# RMS_to_DC.net
KiCad netlist of a schematic drawn in Altium Designer
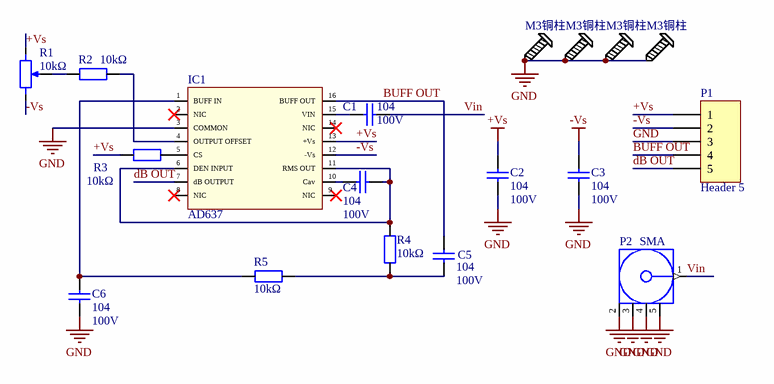
[diagram p0: RMS_to_DC.SchDoc]

(export (version "E")
  (design (tool "Eeschema 10.0.6"))
  (components
    (comp (ref "C1")
      (value "叠层陶瓷电容")
      (footprint "C0603")
      (description "无极性电容")
      (fields (field (name "CAPACITY") "104") (field (name "VOLTAGE") "100V"))
      (libsource (lib "原理图库") (part "104"))
    )
    (comp (ref "C2")
      (value "叠层陶瓷电容")
      (footprint "C0603")
      (description "无极性电容")
      (fields (field (name "CAPACITY") "104") (field (name "VOLTAGE") "100V"))
      (libsource (lib "原理图库") (part "104"))
    )
    (comp (ref "C3")
      (value "叠层陶瓷电容")
      (footprint "C0603")
      (description "无极性电容")
      (fields (field (name "CAPACITY") "104") (field (name "VOLTAGE") "100V"))
      (libsource (lib "原理图库") (part "104"))
    )
    (comp (ref "C4")
      (value "叠层陶瓷电容")
      (footprint "C0603")
      (description "无极性电容")
      (fields (field (name "CAPACITY") "104") (field (name "VOLTAGE") "100V"))
      (libsource (lib "原理图库") (part "104"))
    )
    (comp (ref "C5")
      (value "叠层陶瓷电容")
      (footprint "C0603")
      (description "无极性电容")
      (fields (field (name "CAPACITY") "104") (field (name "VOLTAGE") "100V"))
      (libsource (lib "原理图库") (part "104"))
    )
    (comp (ref "C6")
      (value "叠层陶瓷电容")
      (footprint "C0603")
      (description "无极性电容")
      (fields (field (name "CAPACITY") "104") (field (name "VOLTAGE") "100V"))
      (libsource (lib "原理图库") (part "104"))
    )
    (comp (ref "IC1")
      (value "AD637")
      (footprint "SOP-16(体宽7.5mm)")
      (description "RMS TO DC均方根转换芯片")
      (libsource (lib "原理图库") (part "AD637"))
    )
    (comp (ref "P1")
      (value "Header 5")
      (footprint "HDR1X5")
      (description "Header, 5-Pin")
      (fields (field (name "PUBLISHER") "Altium Limited"))
      (libsource (lib "Miscellaneous Connectors") (part "Header 5"))
    )
    (comp (ref "P2")
      (value "SMA")
      (footprint "SMA-夹板")
      (description "射频座")
      (libsource (lib "原理图库") (part "SMA"))
    )
    (comp (ref "R1")
      (value "10kΩ")
      (footprint "3296W-103")
      (description "三脚可调式电位器")
      (libsource (lib "原理图库") (part "100kΩ"))
    )
    (comp (ref "R2")
      (value "贴片电阻")
      (footprint "R0603")
      (description "贴片/直插电阻")
      (fields (field (name "RESISTANCE") "10kΩ"))
      (libsource (lib "原理图库") (part "10kΩ"))
    )
    (comp (ref "R3")
      (value "贴片电阻")
      (footprint "R0603")
      (description "贴片/直插电阻")
      (fields (field (name "RESISTANCE") "10kΩ"))
      (libsource (lib "原理图库") (part "10kΩ"))
    )
    (comp (ref "R4")
      (value "贴片电阻")
      (footprint "R0603")
      (description "贴片/直插电阻")
      (fields (field (name "RESISTANCE") "10kΩ"))
      (libsource (lib "原理图库") (part "10kΩ"))
    )
    (comp (ref "R5")
      (value "贴片电阻")
      (footprint "R0603")
      (description "贴片/直插电阻")
      (fields (field (name "RESISTANCE") "10kΩ"))
      (libsource (lib "原理图库") (part "10kΩ"))
    )
    (comp (ref "S1") (value "M3铜柱") (footprint "M3") (libsource (lib "原理图库") (part "M3铜柱")))
    (comp (ref "S2") (value "M3铜柱") (footprint "M3") (libsource (lib "原理图库") (part "M3铜柱")))
    (comp (ref "S3") (value "M3铜柱") (footprint "M3") (libsource (lib "原理图库") (part "M3铜柱")))
    (comp (ref "S4") (value "M3铜柱") (footprint "M3") (libsource (lib "原理图库") (part "M3铜柱")))
  )
  (nets
    (net (code "1") (name "+Vs") (class "Default")
      (node (ref "C2") (pin "2") (pintype "passive"))
      (node (ref "IC1") (pin "13") (pinfunction "+Vs_13") (pintype "passive"))
      (node (ref "P1") (pin "1") (pinfunction "1_1") (pintype "passive"))
      (node (ref "R1") (pin "3") (pinfunction "3_3") (pintype "passive"))
      (node (ref "R3") (pin "1") (pintype "passive"))
    )
    (net (code "2") (name "-Vs") (class "Default")
      (node (ref "C3") (pin "2") (pintype "passive"))
      (node (ref "IC1") (pin "12") (pinfunction "-Vs_12") (pintype "passive"))
      (node (ref "P1") (pin "2") (pinfunction "2_2") (pintype "passive"))
      (node (ref "R1") (pin "1") (pinfunction "1_1") (pintype "passive"))
    )
    (net (code "3") (name "/BUFF OUT") (class "Default")
      (node (ref "C5") (pin "2") (pintype "passive"))
      (node (ref "IC1") (pin "16") (pinfunction "BUFF_OUT_16") (pintype "passive"))
      (node (ref "P1") (pin "4") (pinfunction "4_4") (pintype "passive"))
    )
    (net (code "4") (name "/Vin") (class "Default")
      (node (ref "C1") (pin "2") (pintype "passive"))
      (node (ref "P2") (pin "1") (pinfunction "1_1") (pintype "output"))
    )
    (net (code "5") (name "/dB OUT") (class "Default")
      (node (ref "IC1") (pin "7") (pinfunction "dB_OUTPUT_7") (pintype "passive"))
      (node (ref "P1") (pin "5") (pinfunction "5_5") (pintype "passive"))
    )
    (net (code "6") (name "GND") (class "Default")
      (node (ref "C2") (pin "1") (pintype "passive"))
      (node (ref "C3") (pin "1") (pintype "passive"))
      (node (ref "C6") (pin "1") (pintype "passive"))
      (node (ref "IC1") (pin "3") (pinfunction "COMMON_3") (pintype "passive"))
      (node (ref "P1") (pin "3") (pinfunction "3_3") (pintype "passive"))
      (node (ref "P2") (pin "2") (pinfunction "2_2") (pintype "passive"))
      (node (ref "P2") (pin "3") (pinfunction "3_3") (pintype "passive"))
      (node (ref "P2") (pin "4") (pinfunction "4_4") (pintype "passive"))
      (node (ref "P2") (pin "5") (pinfunction "5_5") (pintype "passive"))
      (node (ref "S1") (pin "1") (pinfunction "GND_1") (pintype "passive"))
      (node (ref "S2") (pin "1") (pinfunction "GND_1") (pintype "passive"))
      (node (ref "S3") (pin "1") (pinfunction "GND_1") (pintype "passive"))
      (node (ref "S4") (pin "1") (pinfunction "GND_1") (pintype "passive"))
    )
    (net (code "7") (name "Net-(C5-Pad1)") (class "Default")
      (node (ref "C5") (pin "1") (pintype "passive"))
      (node (ref "R4") (pin "1") (pintype "passive"))
      (node (ref "R5") (pin "2") (pintype "passive"))
    )
    (net (code "8") (name "Net-(IC1-BUFF_IN)") (class "Default")
      (node (ref "C6") (pin "2") (pintype "passive"))
      (node (ref "IC1") (pin "1") (pinfunction "BUFF_IN_1") (pintype "passive"))
      (node (ref "R5") (pin "1") (pintype "passive"))
    )
    (net (code "9") (name "Net-(IC1-CS)") (class "Default")
      (node (ref "IC1") (pin "5") (pinfunction "CS_5") (pintype "passive"))
      (node (ref "R3") (pin "2") (pintype "passive"))
    )
    (net (code "10") (name "Net-(IC1-Cav)") (class "Default")
      (node (ref "C4") (pin "1") (pintype "passive"))
      (node (ref "IC1") (pin "10") (pinfunction "Cav_10") (pintype "passive"))
    )
    (net (code "11") (name "Net-(IC1-DEN_INPUT)") (class "Default")
      (node (ref "C4") (pin "2") (pintype "passive"))
      (node (ref "IC1") (pin "11") (pinfunction "RMS_OUT_11") (pintype "passive"))
      (node (ref "IC1") (pin "6") (pinfunction "DEN_INPUT_6") (pintype "passive"))
      (node (ref "R4") (pin "2") (pintype "passive"))
    )
    (net (code "12") (name "Net-(IC1-OUTPUT_OFFSET)") (class "Default")
      (node (ref "IC1") (pin "4") (pinfunction "OUTPUT_OFFSET_4") (pintype "passive"))
      (node (ref "R2") (pin "2") (pintype "passive"))
    )
    (net (code "13") (name "Net-(IC1-VIN)") (class "Default")
      (node (ref "C1") (pin "1") (pintype "passive"))
      (node (ref "IC1") (pin "15") (pinfunction "VIN_15") (pintype "passive"))
    )
    (net (code "14") (name "Net-(R1-Pad2)") (class "Default")
      (node (ref "R1") (pin "2") (pinfunction "2_2") (pintype "passive"))
      (node (ref "R2") (pin "1") (pintype "passive"))
    )
    (net (code "15") (name "unconnected-(IC1-NIC-Pad2)") (class "Default")
      (node (ref "IC1") (pin "2") (pinfunction "NIC_2") (pintype "passive+no_connect"))
    )
    (net (code "16") (name "unconnected-(IC1-NIC-Pad8)") (class "Default")
      (node (ref "IC1") (pin "8") (pinfunction "NIC_8") (pintype "passive+no_connect"))
    )
    (net (code "17") (name "unconnected-(IC1-NIC-Pad9)") (class "Default")
      (node (ref "IC1") (pin "9") (pinfunction "NIC_9") (pintype "passive+no_connect"))
    )
    (net (code "18") (name "unconnected-(IC1-NIC-Pad14)") (class "Default")
      (node (ref "IC1") (pin "14") (pinfunction "NIC_14") (pintype "passive+no_connect"))
    )
  )
)
